# Schaltkasten.net
KiCad netlist of a schematic drawn in EAGLE
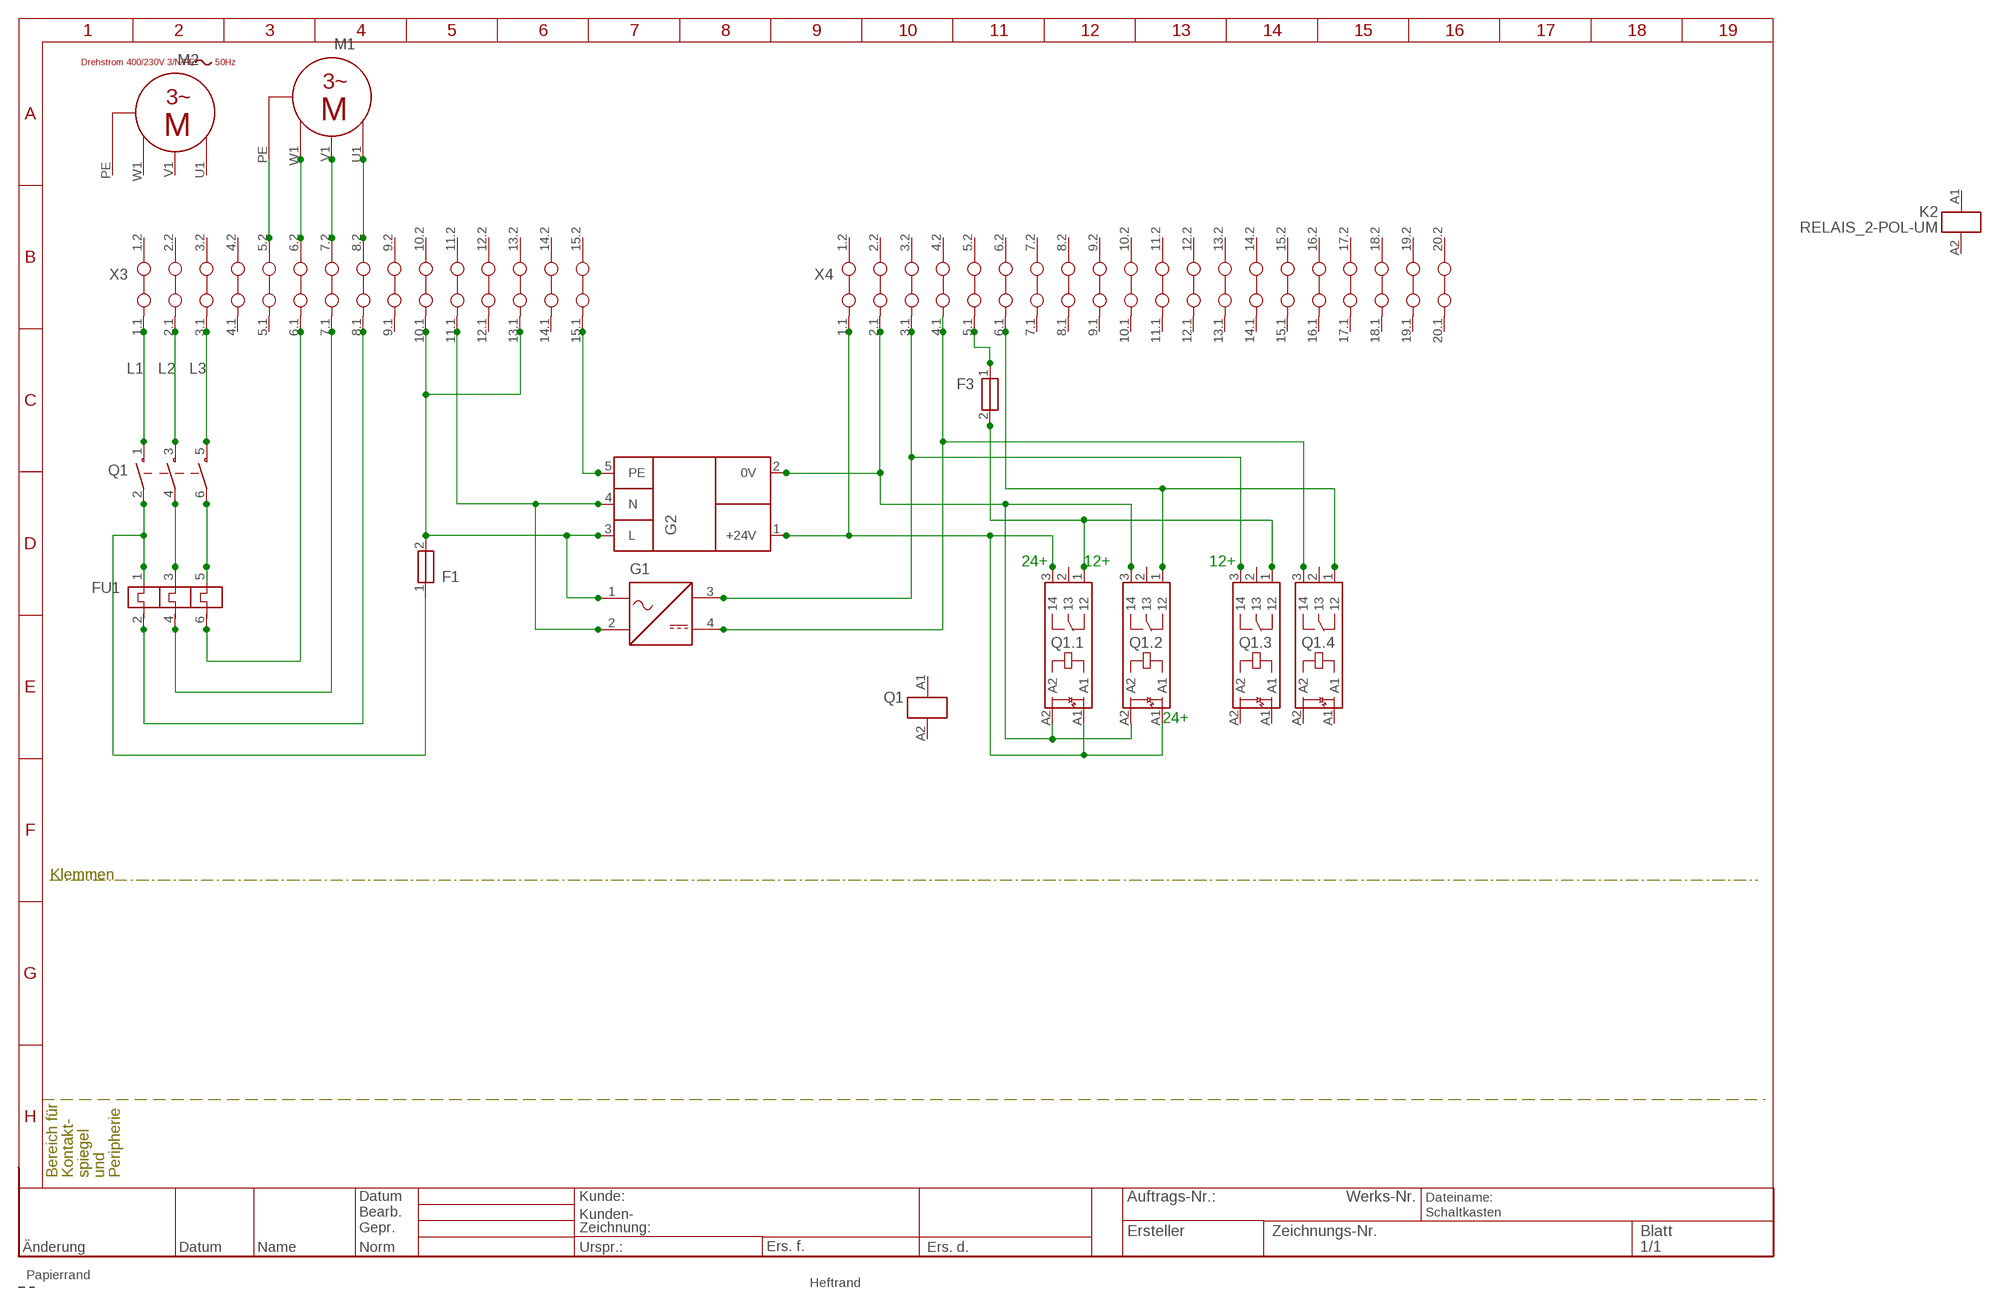
[diagram p0: schematic, sheet 1]

(export (version "E")
  (design (tool "Eeschema 10.0.6"))
  (components
    (comp (ref "F1")
      (value "SICHERUNG_1-POL")
      (footprint "eagle-import:SICHERUNG_1-POL")
      (libsource (lib "eagle-import") (part "SICHERUNG_1-POL"))
    )
    (comp (ref "F3")
      (value "SICHERUNG_1-POL")
      (footprint "eagle-import:SICHERUNG_1-POL")
      (libsource (lib "eagle-import") (part "SICHERUNG_1-POL"))
    )
    (comp (ref "FU1")
      (value "MOTORSCHUTZSCHALTER_3-POL_THERM_AUSLOESUNG_ALTERNATIV")
      (footprint "eagle-import:MOTORSCHUTZSCHALTER_3-POL_THERM_AUSLOESUNG_ALTERNATIV")
      (libsource (lib "eagle-import") (part "MOTORSCHUTZSCHALTER_3-POL_THERM_AUSLOESUNG_ALTERNATIV"))
    )
    (comp (ref "G1")
      (value "NETZTEIL_GLEICHSPANNUNG")
      (footprint "eagle-import:NETZTEIL_GLEICHSPANNUNG")
      (libsource (lib "eagle-import") (part "NETZTEIL_GLEICHSPANNUNG"))
    )
    (comp (ref "G2")
      (value "NETZTEIL_MURR_24V")
      (footprint "eagle-import:NETZTEIL_MURR_24V")
      (libsource (lib "eagle-import") (part "NETZTEIL_MURR_24V"))
    )
    (comp (ref "K2")
      (value "RELAIS_2-POL-UM")
      (footprint "eagle-import:RELAIS_2-POL-UM")
      (libsource (lib "eagle-import") (part "RELAIS_2-POL-UM"))
    )
    (comp (ref "M1")
      (value "MOTOR_3-POL_PE")
      (footprint "eagle-import:MOTOR_3-POL_PE")
      (libsource (lib "eagle-import") (part "MOTOR_3-POL_PE"))
    )
    (comp (ref "M2")
      (value "MOTOR_3-POL_PE")
      (footprint "eagle-import:MOTOR_3-POL_PE")
      (libsource (lib "eagle-import") (part "MOTOR_3-POL_PE"))
    )
    (comp (ref "Q1")
      (value "HAUPTSCHUETZ_3-POL")
      (footprint "eagle-import:HAUPTSCHUETZ_3-POL")
      (libsource (lib "eagle-import") (part "HAUPTSCHUETZ_3-POL"))
    )
    (comp (ref "Q1.1")
      (value "RELAISKLEMME_MIT_LED")
      (footprint "eagle-import:RELAISKLEMME_MIT_LED")
      (libsource (lib "eagle-import") (part "RELAISKLEMME_MIT_LED"))
    )
    (comp (ref "Q1.2")
      (value "RELAISKLEMME_MIT_LED")
      (footprint "eagle-import:RELAISKLEMME_MIT_LED")
      (libsource (lib "eagle-import") (part "RELAISKLEMME_MIT_LED"))
    )
    (comp (ref "Q1.3")
      (value "RELAISKLEMME_MIT_LED")
      (footprint "eagle-import:RELAISKLEMME_MIT_LED")
      (libsource (lib "eagle-import") (part "RELAISKLEMME_MIT_LED"))
    )
    (comp (ref "Q1.4")
      (value "RELAISKLEMME_MIT_LED")
      (footprint "eagle-import:RELAISKLEMME_MIT_LED")
      (libsource (lib "eagle-import") (part "RELAISKLEMME_MIT_LED"))
    )
    (comp (ref "X3")
      (value "KLEMME_2-15")
      (footprint "eagle-import:KLEMME_2-15")
      (libsource (lib "eagle-import") (part "KLEMME_2-15"))
    )
    (comp (ref "X4")
      (value "KLEMME_2-20")
      (footprint "eagle-import:KLEMME_2-20")
      (libsource (lib "eagle-import") (part "KLEMME_2-20"))
    )
  )
  (nets
    (net (code "1") (name "/L1") (class "Default")
      (node (ref "Q1") (pin "1") (pinfunction "1_1") (pintype "passive"))
      (node (ref "X3") (pin "1.1") (pinfunction "1.1_1.1") (pintype "passive"))
    )
    (net (code "2") (name "/L2") (class "Default")
      (node (ref "Q1") (pin "3") (pinfunction "3_3") (pintype "passive"))
      (node (ref "X3") (pin "2.1") (pinfunction "2.1_2.1") (pintype "passive"))
    )
    (net (code "3") (name "/L3") (class "Default")
      (node (ref "Q1") (pin "5") (pinfunction "5_5") (pintype "passive"))
      (node (ref "X3") (pin "3.1") (pinfunction "3.1_3.1") (pintype "passive"))
    )
    (net (code "4") (name "Net-(F1-Pad1)") (class "Default")
      (node (ref "F1") (pin "1") (pinfunction "1_1") (pintype "passive"))
      (node (ref "FU1") (pin "1") (pinfunction "1_1") (pintype "passive"))
      (node (ref "Q1") (pin "2") (pinfunction "2_2") (pintype "passive"))
    )
    (net (code "5") (name "Net-(F3-Pad1)") (class "Default")
      (node (ref "F3") (pin "1") (pinfunction "1_1") (pintype "passive"))
      (node (ref "X4") (pin "5.1") (pinfunction "5.1_5.1") (pintype "passive"))
    )
    (net (code "6") (name "Net-(FU1-Pad2)") (class "Default")
      (node (ref "FU1") (pin "2") (pinfunction "2_2") (pintype "passive"))
      (node (ref "X3") (pin "8.1") (pinfunction "8.1_8.1") (pintype "passive"))
    )
    (net (code "7") (name "Net-(FU1-Pad3)") (class "Default")
      (node (ref "FU1") (pin "3") (pinfunction "3_3") (pintype "passive"))
      (node (ref "Q1") (pin "4") (pinfunction "4_4") (pintype "passive"))
    )
    (net (code "8") (name "Net-(FU1-Pad4)") (class "Default")
      (node (ref "FU1") (pin "4") (pinfunction "4_4") (pintype "passive"))
      (node (ref "X3") (pin "7.1") (pinfunction "7.1_7.1") (pintype "passive"))
    )
    (net (code "9") (name "Net-(FU1-Pad5)") (class "Default")
      (node (ref "FU1") (pin "5") (pinfunction "5_5") (pintype "passive"))
      (node (ref "Q1") (pin "6") (pinfunction "6_6") (pintype "passive"))
    )
    (net (code "10") (name "Net-(FU1-Pad6)") (class "Default")
      (node (ref "FU1") (pin "6") (pinfunction "6_6") (pintype "passive"))
      (node (ref "X3") (pin "6.1") (pinfunction "6.1_6.1") (pintype "passive"))
    )
    (net (code "11") (name "Net-(G2-+24V)") (class "Default")
      (node (ref "G2") (pin "1") (pinfunction "+24V_1") (pintype "passive"))
      (node (ref "Q1.1") (pin "3") (pinfunction "14_3") (pintype "passive"))
      (node (ref "Q1.1") (pin "A1") (pinfunction "A1_A1") (pintype "passive"))
      (node (ref "Q1.2") (pin "A1") (pinfunction "A1_A1") (pintype "passive"))
      (node (ref "X4") (pin "1.1") (pinfunction "1.1_1.1") (pintype "passive"))
    )
    (net (code "12") (name "Net-(G2-0V)") (class "Default")
      (node (ref "G2") (pin "2") (pinfunction "0V_2") (pintype "passive"))
      (node (ref "Q1.1") (pin "A2") (pinfunction "A2_A2") (pintype "passive"))
      (node (ref "Q1.2") (pin "3") (pinfunction "14_3") (pintype "passive"))
      (node (ref "Q1.2") (pin "A2") (pinfunction "A2_A2") (pintype "passive"))
      (node (ref "X4") (pin "2.1") (pinfunction "2.1_2.1") (pintype "passive"))
    )
    (net (code "13") (name "Net-(G2-L)") (class "Default")
      (node (ref "F1") (pin "2") (pinfunction "2_2") (pintype "passive"))
      (node (ref "G1") (pin "1") (pinfunction "1_1") (pintype "passive"))
      (node (ref "G2") (pin "3") (pinfunction "L_3") (pintype "input"))
      (node (ref "X3") (pin "10.1") (pinfunction "10.1_10.1") (pintype "passive"))
      (node (ref "X3") (pin "13.1") (pinfunction "13.1_13.1") (pintype "passive"))
    )
    (net (code "14") (name "Net-(G2-N)") (class "Default")
      (node (ref "G1") (pin "2") (pinfunction "2_2") (pintype "passive"))
      (node (ref "G2") (pin "4") (pinfunction "N_4") (pintype "input"))
      (node (ref "X3") (pin "11.1") (pinfunction "11.1_11.1") (pintype "passive"))
    )
    (net (code "15") (name "Net-(G2-PE)") (class "Default")
      (node (ref "G2") (pin "5") (pinfunction "PE_5") (pintype "input"))
      (node (ref "X3") (pin "15.1") (pinfunction "15.1_15.1") (pintype "passive"))
    )
    (net (code "16") (name "Net-(M1-PadPE)") (class "Default")
      (node (ref "M1") (pin "PE") (pinfunction "PE_PE") (pintype "passive"))
      (node (ref "X3") (pin "5.2") (pinfunction "5.2_5.2") (pintype "passive"))
    )
    (net (code "17") (name "Net-(M1-PadU1)") (class "Default")
      (node (ref "M1") (pin "U1") (pinfunction "U1_U1") (pintype "passive"))
      (node (ref "X3") (pin "8.2") (pinfunction "8.2_8.2") (pintype "passive"))
    )
    (net (code "18") (name "Net-(M1-PadV1)") (class "Default")
      (node (ref "M1") (pin "V1") (pinfunction "V1_V1") (pintype "passive"))
      (node (ref "X3") (pin "7.2") (pinfunction "7.2_7.2") (pintype "passive"))
    )
    (net (code "19") (name "Net-(M1-PadW1)") (class "Default")
      (node (ref "M1") (pin "W1") (pinfunction "W1_W1") (pintype "passive"))
      (node (ref "X3") (pin "6.2") (pinfunction "6.2_6.2") (pintype "passive"))
    )
    (net (code "20") (name "Net-(Q1.1-12)") (class "Default")
      (node (ref "F3") (pin "2") (pinfunction "2_2") (pintype "passive"))
      (node (ref "Q1.1") (pin "1") (pinfunction "12_1") (pintype "passive"))
      (node (ref "Q1.3") (pin "1") (pinfunction "12_1") (pintype "passive"))
    )
    (net (code "21") (name "Net-(Q1.2-12)") (class "Default")
      (node (ref "Q1.2") (pin "1") (pinfunction "12_1") (pintype "passive"))
      (node (ref "Q1.4") (pin "1") (pinfunction "12_1") (pintype "passive"))
      (node (ref "X4") (pin "6.1") (pinfunction "6.1_6.1") (pintype "passive"))
    )
    (net (code "22") (name "Net-(Q1.3-14)") (class "Default")
      (node (ref "G1") (pin "3") (pinfunction "3_3") (pintype "passive"))
      (node (ref "Q1.3") (pin "3") (pinfunction "14_3") (pintype "passive"))
      (node (ref "X4") (pin "3.1") (pinfunction "3.1_3.1") (pintype "passive"))
    )
    (net (code "23") (name "Net-(Q1.4-14)") (class "Default")
      (node (ref "G1") (pin "4") (pinfunction "4_4") (pintype "passive"))
      (node (ref "Q1.4") (pin "3") (pinfunction "14_3") (pintype "passive"))
      (node (ref "X4") (pin "4.1") (pinfunction "4.1_4.1") (pintype "passive"))
    )
    (net (code "24") (name "unconnected-(K2-PadA1)") (class "Default")
      (node (ref "K2") (pin "A1") (pinfunction "A1_A1") (pintype "input"))
    )
    (net (code "25") (name "unconnected-(K2-PadA2)") (class "Default")
      (node (ref "K2") (pin "A2") (pinfunction "A2_A2") (pintype "input"))
    )
    (net (code "26") (name "unconnected-(M2-PadPE)") (class "Default")
      (node (ref "M2") (pin "PE") (pinfunction "PE_PE") (pintype "passive"))
    )
    (net (code "27") (name "unconnected-(M2-PadU1)") (class "Default")
      (node (ref "M2") (pin "U1") (pinfunction "U1_U1") (pintype "passive"))
    )
    (net (code "28") (name "unconnected-(M2-PadV1)") (class "Default")
      (node (ref "M2") (pin "V1") (pinfunction "V1_V1") (pintype "passive"))
    )
    (net (code "29") (name "unconnected-(M2-PadW1)") (class "Default")
      (node (ref "M2") (pin "W1") (pinfunction "W1_W1") (pintype "passive"))
    )
    (net (code "30") (name "unconnected-(Q1-PadA1)") (class "Default")
      (node (ref "Q1") (pin "A1") (pinfunction "A1_A1") (pintype "input"))
    )
    (net (code "31") (name "unconnected-(Q1-PadA2)") (class "Default")
      (node (ref "Q1") (pin "A2") (pinfunction "A2_A2") (pintype "input"))
    )
    (net (code "32") (name "unconnected-(Q1.1-13-Pad2)") (class "Default")
      (node (ref "Q1.1") (pin "2") (pinfunction "13_2") (pintype "passive"))
    )
    (net (code "33") (name "unconnected-(Q1.2-13-Pad2)") (class "Default")
      (node (ref "Q1.2") (pin "2") (pinfunction "13_2") (pintype "passive"))
    )
    (net (code "34") (name "unconnected-(Q1.3-13-Pad2)") (class "Default")
      (node (ref "Q1.3") (pin "2") (pinfunction "13_2") (pintype "passive"))
    )
    (net (code "35") (name "unconnected-(Q1.3-PadA1)") (class "Default")
      (node (ref "Q1.3") (pin "A1") (pinfunction "A1_A1") (pintype "passive"))
    )
    (net (code "36") (name "unconnected-(Q1.3-PadA2)") (class "Default")
      (node (ref "Q1.3") (pin "A2") (pinfunction "A2_A2") (pintype "passive"))
    )
    (net (code "37") (name "unconnected-(Q1.4-13-Pad2)") (class "Default")
      (node (ref "Q1.4") (pin "2") (pinfunction "13_2") (pintype "passive"))
    )
    (net (code "38") (name "unconnected-(Q1.4-PadA1)") (class "Default")
      (node (ref "Q1.4") (pin "A1") (pinfunction "A1_A1") (pintype "passive"))
    )
    (net (code "39") (name "unconnected-(Q1.4-PadA2)") (class "Default")
      (node (ref "Q1.4") (pin "A2") (pinfunction "A2_A2") (pintype "passive"))
    )
    (net (code "40") (name "unconnected-(X3-Pad1.2)") (class "Default")
      (node (ref "X3") (pin "1.2") (pinfunction "1.2_1.2") (pintype "passive"))
    )
    (net (code "41") (name "unconnected-(X3-Pad2.2)") (class "Default")
      (node (ref "X3") (pin "2.2") (pinfunction "2.2_2.2") (pintype "passive"))
    )
    (net (code "42") (name "unconnected-(X3-Pad3.2)") (class "Default")
      (node (ref "X3") (pin "3.2") (pinfunction "3.2_3.2") (pintype "passive"))
    )
    (net (code "43") (name "unconnected-(X3-Pad4.1)") (class "Default")
      (node (ref "X3") (pin "4.1") (pinfunction "4.1_4.1") (pintype "passive"))
    )
    (net (code "44") (name "unconnected-(X3-Pad4.2)") (class "Default")
      (node (ref "X3") (pin "4.2") (pinfunction "4.2_4.2") (pintype "passive"))
    )
    (net (code "45") (name "unconnected-(X3-Pad5.1)") (class "Default")
      (node (ref "X3") (pin "5.1") (pinfunction "5.1_5.1") (pintype "passive"))
    )
    (net (code "46") (name "unconnected-(X3-Pad9.1)") (class "Default")
      (node (ref "X3") (pin "9.1") (pinfunction "9.1_9.1") (pintype "passive"))
    )
    (net (code "47") (name "unconnected-(X3-Pad9.2)") (class "Default")
      (node (ref "X3") (pin "9.2") (pinfunction "9.2_9.2") (pintype "passive"))
    )
    (net (code "48") (name "unconnected-(X3-Pad10.2)") (class "Default")
      (node (ref "X3") (pin "10.2") (pinfunction "10.2_10.2") (pintype "passive"))
    )
    (net (code "49") (name "unconnected-(X3-Pad11.2)") (class "Default")
      (node (ref "X3") (pin "11.2") (pinfunction "11.2_11.2") (pintype "passive"))
    )
    (net (code "50") (name "unconnected-(X3-Pad12.1)") (class "Default")
      (node (ref "X3") (pin "12.1") (pinfunction "12.1_12.1") (pintype "passive"))
    )
    (net (code "51") (name "unconnected-(X3-Pad12.2)") (class "Default")
      (node (ref "X3") (pin "12.2") (pinfunction "12.2_12.2") (pintype "passive"))
    )
    (net (code "52") (name "unconnected-(X3-Pad13.2)") (class "Default")
      (node (ref "X3") (pin "13.2") (pinfunction "13.2_13.2") (pintype "passive"))
    )
    (net (code "53") (name "unconnected-(X3-Pad14.1)") (class "Default")
      (node (ref "X3") (pin "14.1") (pinfunction "14.1_14.1") (pintype "passive"))
    )
    (net (code "54") (name "unconnected-(X3-Pad14.2)") (class "Default")
      (node (ref "X3") (pin "14.2") (pinfunction "14.2_14.2") (pintype "passive"))
    )
    (net (code "55") (name "unconnected-(X3-Pad15.2)") (class "Default")
      (node (ref "X3") (pin "15.2") (pinfunction "15.2_15.2") (pintype "passive"))
    )
    (net (code "56") (name "unconnected-(X4-Pad1.2)") (class "Default")
      (node (ref "X4") (pin "1.2") (pinfunction "1.2_1.2") (pintype "passive"))
    )
    (net (code "57") (name "unconnected-(X4-Pad2.2)") (class "Default")
      (node (ref "X4") (pin "2.2") (pinfunction "2.2_2.2") (pintype "passive"))
    )
    (net (code "58") (name "unconnected-(X4-Pad3.2)") (class "Default")
      (node (ref "X4") (pin "3.2") (pinfunction "3.2_3.2") (pintype "passive"))
    )
    (net (code "59") (name "unconnected-(X4-Pad4.2)") (class "Default")
      (node (ref "X4") (pin "4.2") (pinfunction "4.2_4.2") (pintype "passive"))
    )
    (net (code "60") (name "unconnected-(X4-Pad5.2)") (class "Default")
      (node (ref "X4") (pin "5.2") (pinfunction "5.2_5.2") (pintype "passive"))
    )
    (net (code "61") (name "unconnected-(X4-Pad6.2)") (class "Default")
      (node (ref "X4") (pin "6.2") (pinfunction "6.2_6.2") (pintype "passive"))
    )
    (net (code "62") (name "unconnected-(X4-Pad7.1)") (class "Default")
      (node (ref "X4") (pin "7.1") (pinfunction "7.1_7.1") (pintype "passive"))
    )
    (net (code "63") (name "unconnected-(X4-Pad7.2)") (class "Default")
      (node (ref "X4") (pin "7.2") (pinfunction "7.2_7.2") (pintype "passive"))
    )
    (net (code "64") (name "unconnected-(X4-Pad8.1)") (class "Default")
      (node (ref "X4") (pin "8.1") (pinfunction "8.1_8.1") (pintype "passive"))
    )
    (net (code "65") (name "unconnected-(X4-Pad8.2)") (class "Default")
      (node (ref "X4") (pin "8.2") (pinfunction "8.2_8.2") (pintype "passive"))
    )
    (net (code "66") (name "unconnected-(X4-Pad9.1)") (class "Default")
      (node (ref "X4") (pin "9.1") (pinfunction "9.1_9.1") (pintype "passive"))
    )
    (net (code "67") (name "unconnected-(X4-Pad9.2)") (class "Default")
      (node (ref "X4") (pin "9.2") (pinfunction "9.2_9.2") (pintype "passive"))
    )
    (net (code "68") (name "unconnected-(X4-Pad10.1)") (class "Default")
      (node (ref "X4") (pin "10.1") (pinfunction "10.1_10.1") (pintype "passive"))
    )
    (net (code "69") (name "unconnected-(X4-Pad10.2)") (class "Default")
      (node (ref "X4") (pin "10.2") (pinfunction "10.2_10.2") (pintype "passive"))
    )
    (net (code "70") (name "unconnected-(X4-Pad11.1)") (class "Default")
      (node (ref "X4") (pin "11.1") (pinfunction "11.1_11.1") (pintype "passive"))
    )
    (net (code "71") (name "unconnected-(X4-Pad11.2)") (class "Default")
      (node (ref "X4") (pin "11.2") (pinfunction "11.2_11.2") (pintype "passive"))
    )
    (net (code "72") (name "unconnected-(X4-Pad12.1)") (class "Default")
      (node (ref "X4") (pin "12.1") (pinfunction "12.1_12.1") (pintype "passive"))
    )
    (net (code "73") (name "unconnected-(X4-Pad12.2)") (class "Default")
      (node (ref "X4") (pin "12.2") (pinfunction "12.2_12.2") (pintype "passive"))
    )
    (net (code "74") (name "unconnected-(X4-Pad13.1)") (class "Default")
      (node (ref "X4") (pin "13.1") (pinfunction "13.1_13.1") (pintype "passive"))
    )
    (net (code "75") (name "unconnected-(X4-Pad13.2)") (class "Default")
      (node (ref "X4") (pin "13.2") (pinfunction "13.2_13.2") (pintype "passive"))
    )
    (net (code "76") (name "unconnected-(X4-Pad14.1)") (class "Default")
      (node (ref "X4") (pin "14.1") (pinfunction "14.1_14.1") (pintype "passive"))
    )
    (net (code "77") (name "unconnected-(X4-Pad14.2)") (class "Default")
      (node (ref "X4") (pin "14.2") (pinfunction "14.2_14.2") (pintype "passive"))
    )
    (net (code "78") (name "unconnected-(X4-Pad15.1)") (class "Default")
      (node (ref "X4") (pin "15.1") (pinfunction "15.1_15.1") (pintype "passive"))
    )
    (net (code "79") (name "unconnected-(X4-Pad15.2)") (class "Default")
      (node (ref "X4") (pin "15.2") (pinfunction "15.2_15.2") (pintype "passive"))
    )
    (net (code "80") (name "unconnected-(X4-Pad16.1)") (class "Default")
      (node (ref "X4") (pin "16.1") (pinfunction "16.1_16.1") (pintype "passive"))
    )
    (net (code "81") (name "unconnected-(X4-Pad16.2)") (class "Default")
      (node (ref "X4") (pin "16.2") (pinfunction "16.2_16.2") (pintype "passive"))
    )
    (net (code "82") (name "unconnected-(X4-Pad17.1)") (class "Default")
      (node (ref "X4") (pin "17.1") (pinfunction "17.1_17.1") (pintype "passive"))
    )
    (net (code "83") (name "unconnected-(X4-Pad17.2)") (class "Default")
      (node (ref "X4") (pin "17.2") (pinfunction "17.2_17.2") (pintype "passive"))
    )
    (net (code "84") (name "unconnected-(X4-Pad18.1)") (class "Default")
      (node (ref "X4") (pin "18.1") (pinfunction "18.1_18.1") (pintype "passive"))
    )
    (net (code "85") (name "unconnected-(X4-Pad18.2)") (class "Default")
      (node (ref "X4") (pin "18.2") (pinfunction "18.2_18.2") (pintype "passive"))
    )
    (net (code "86") (name "unconnected-(X4-Pad19.1)") (class "Default")
      (node (ref "X4") (pin "19.1") (pinfunction "19.1_19.1") (pintype "passive"))
    )
    (net (code "87") (name "unconnected-(X4-Pad19.2)") (class "Default")
      (node (ref "X4") (pin "19.2") (pinfunction "19.2_19.2") (pintype "passive"))
    )
    (net (code "88") (name "unconnected-(X4-Pad20.1)") (class "Default")
      (node (ref "X4") (pin "20.1") (pinfunction "20.1_20.1") (pintype "passive"))
    )
    (net (code "89") (name "unconnected-(X4-Pad20.2)") (class "Default")
      (node (ref "X4") (pin "20.2") (pinfunction "20.2_20.2") (pintype "passive"))
    )
  )
)
